# badge.net
KiCad netlist of a schematic drawn in EAGLE
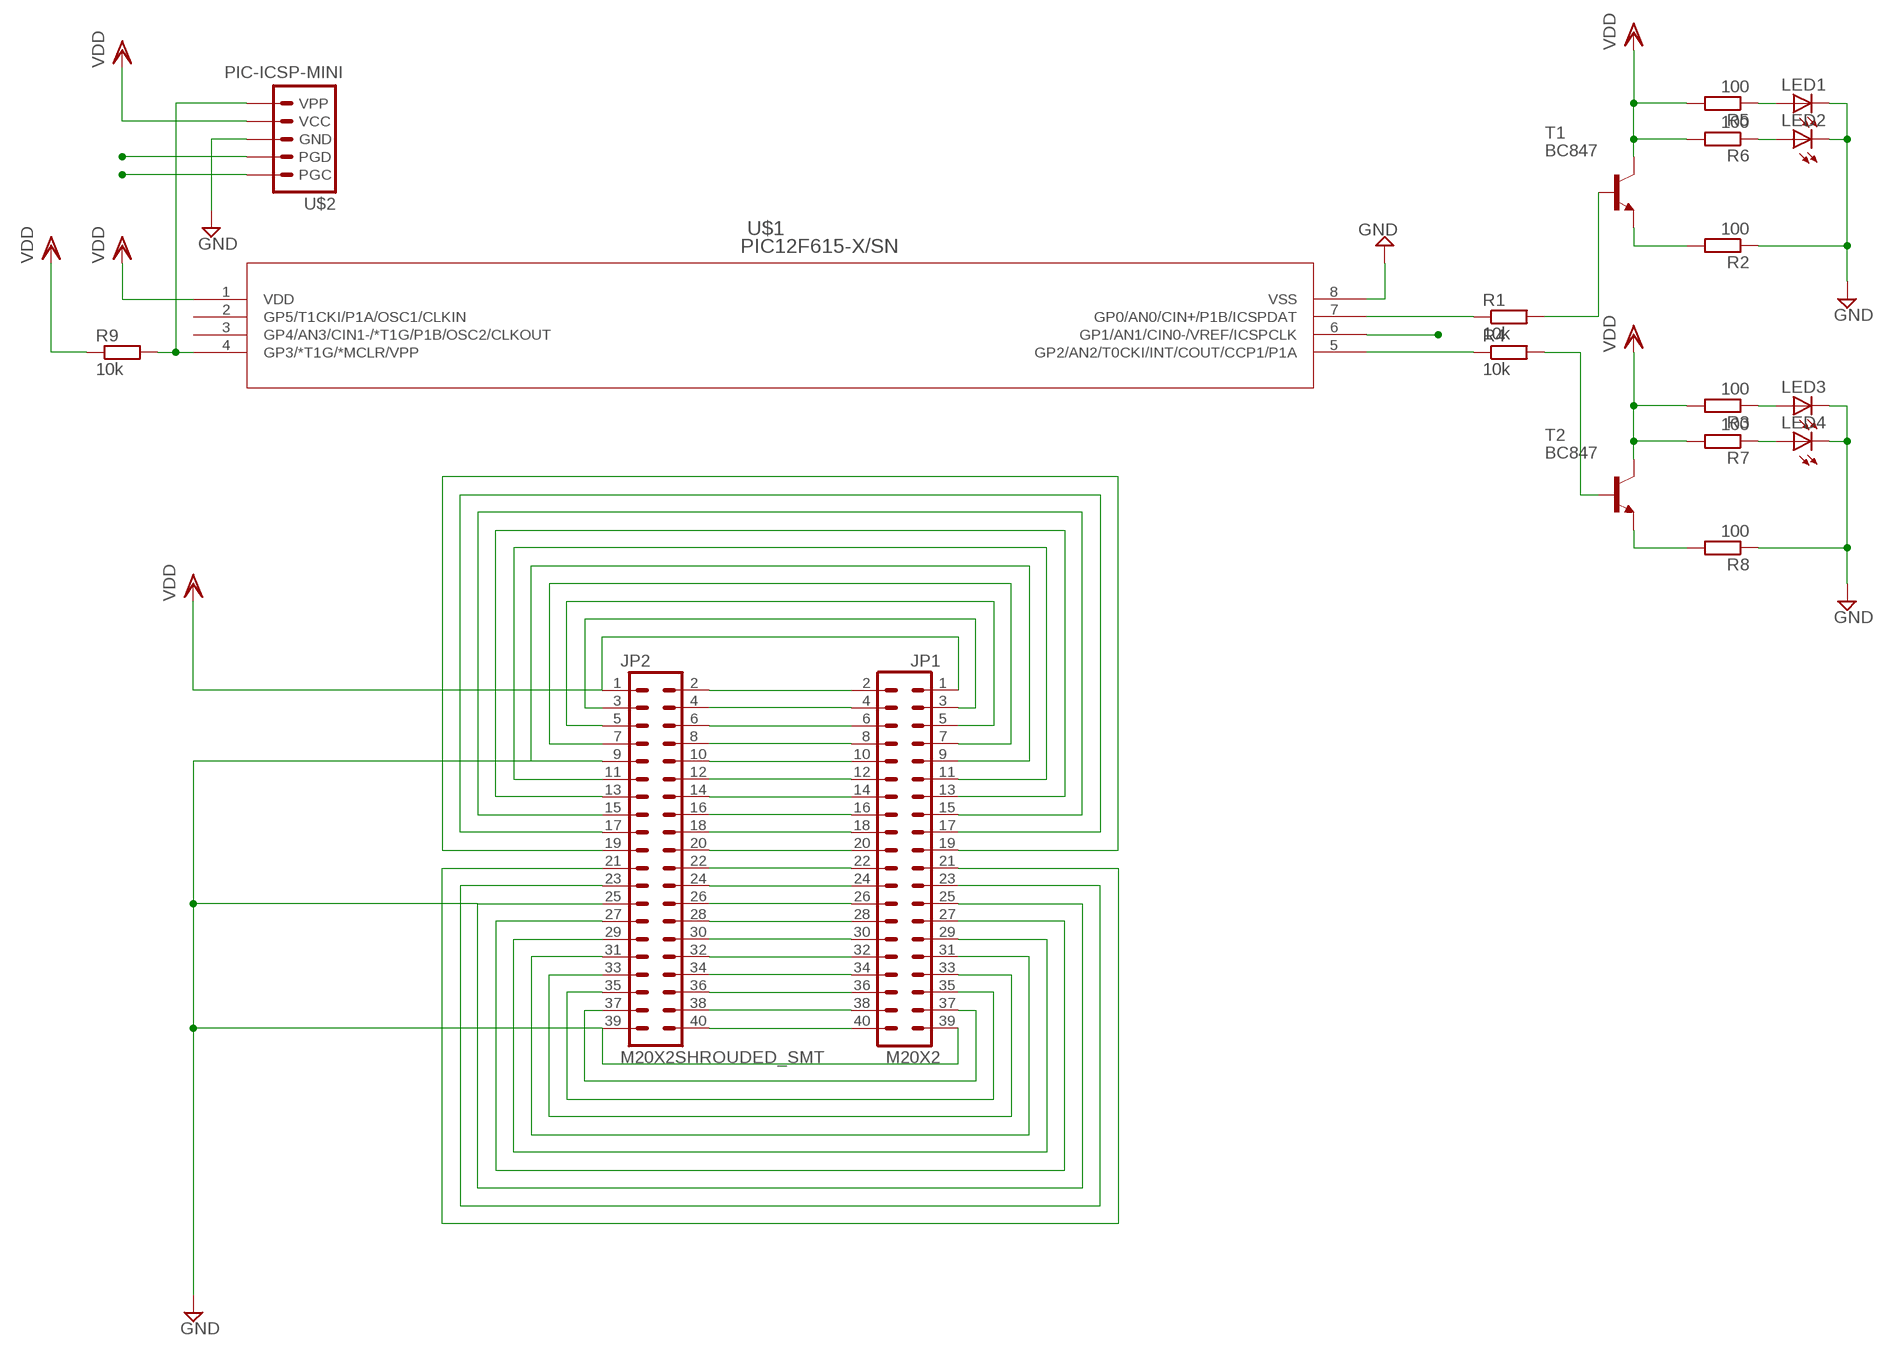
[diagram p0: schematic, sheet 1]

(export (version "E")
  (design (tool "Eeschema 10.0.6"))
  (components
    (comp (ref "JP1")
      (value "M20X2")
      (footprint "eagle-import:2X20")
      (libsource (lib "eagle-import") (part "M20X2"))
    )
    (comp (ref "JP2")
      (value "M20X2SHROUDED_SMT")
      (footprint "eagle-import:2X20_SHROUDED_SMT")
      (libsource (lib "eagle-import") (part "M20X2SHROUDED_SMT"))
    )
    (comp (ref "LED1")
      (value "LEDCHIPLED_0805")
      (footprint "eagle-import:CHIPLED_0805")
      (libsource (lib "eagle-import") (part "LEDCHIPLED_0805"))
    )
    (comp (ref "LED2")
      (value "LEDCHIPLED_0805")
      (footprint "eagle-import:CHIPLED_0805")
      (libsource (lib "eagle-import") (part "LEDCHIPLED_0805"))
    )
    (comp (ref "LED3")
      (value "LEDCHIPLED_0805")
      (footprint "eagle-import:CHIPLED_0805")
      (libsource (lib "eagle-import") (part "LEDCHIPLED_0805"))
    )
    (comp (ref "LED4")
      (value "LEDCHIPLED_0805")
      (footprint "eagle-import:CHIPLED_0805")
      (libsource (lib "eagle-import") (part "LEDCHIPLED_0805"))
    )
    (comp (ref "R1")
      (value "10k")
      (footprint "eagle-import:R0805")
      (libsource (lib "eagle-import") (part "R-EU_R0805"))
    )
    (comp (ref "R2")
      (value "100")
      (footprint "eagle-import:R0805")
      (libsource (lib "eagle-import") (part "R-EU_R0805"))
    )
    (comp (ref "R3")
      (value "100")
      (footprint "eagle-import:R0805")
      (libsource (lib "eagle-import") (part "R-EU_R0805"))
    )
    (comp (ref "R4")
      (value "10k")
      (footprint "eagle-import:R0805")
      (libsource (lib "eagle-import") (part "R-EU_R0805"))
    )
    (comp (ref "R5")
      (value "100")
      (footprint "eagle-import:R0805")
      (libsource (lib "eagle-import") (part "R-EU_R0805"))
    )
    (comp (ref "R6")
      (value "100")
      (footprint "eagle-import:R0805")
      (libsource (lib "eagle-import") (part "R-EU_R0805"))
    )
    (comp (ref "R7")
      (value "100")
      (footprint "eagle-import:R0805")
      (libsource (lib "eagle-import") (part "R-EU_R0805"))
    )
    (comp (ref "R8")
      (value "100")
      (footprint "eagle-import:R0805")
      (libsource (lib "eagle-import") (part "R-EU_R0805"))
    )
    (comp (ref "R9")
      (value "10k")
      (footprint "eagle-import:R0805")
      (libsource (lib "eagle-import") (part "R-EU_R0805"))
    )
    (comp (ref "T1")
      (value "BC847")
      (footprint "eagle-import:SOT23")
      (libsource (lib "eagle-import") (part "BC847"))
    )
    (comp (ref "T2")
      (value "BC847")
      (footprint "eagle-import:SOT23")
      (libsource (lib "eagle-import") (part "BC847"))
    )
    (comp (ref "U$1")
      (value "PIC12F615-X/SN")
      (footprint "eagle-import:SOIC8-N_MC")
      (libsource (lib "eagle-import") (part "PIC12F615-X/SN"))
    )
    (comp (ref "U$2")
      (value "PIC-ICSP-MINI")
      (footprint "eagle-import:PIC-ICSP-MINI")
      (libsource (lib "eagle-import") (part "PIC-ICSP-MINI"))
    )
  )
  (nets
    (net (code "1") (name "/ICSPCLK") (class "Default")
      (node (ref "U$1") (pin "6") (pinfunction "GP1/AN1/CIN0-/VREF/ICSPCLK_6") (pintype "passive"))
      (node (ref "U$2") (pin "5") (pinfunction "PGC_5") (pintype "passive"))
    )
    (net (code "2") (name "/ICSPDAT") (class "Default")
      (node (ref "R1") (pin "1") (pinfunction "1_1") (pintype "passive"))
      (node (ref "U$1") (pin "7") (pinfunction "GP0/AN0/CIN+/P1B/ICSPDAT_7") (pintype "passive"))
      (node (ref "U$2") (pin "4") (pinfunction "PGD_4") (pintype "passive"))
    )
    (net (code "3") (name "GND") (class "Default")
      (node (ref "JP1") (pin "14") (pinfunction "14_14") (pintype "passive"))
      (node (ref "JP1") (pin "20") (pinfunction "20_20") (pintype "passive"))
      (node (ref "JP1") (pin "25") (pinfunction "25_25") (pintype "passive"))
      (node (ref "JP1") (pin "30") (pinfunction "30_30") (pintype "passive"))
      (node (ref "JP1") (pin "34") (pinfunction "34_34") (pintype "passive"))
      (node (ref "JP1") (pin "39") (pinfunction "39_39") (pintype "passive"))
      (node (ref "JP1") (pin "6") (pinfunction "6_6") (pintype "passive"))
      (node (ref "JP1") (pin "9") (pinfunction "9_9") (pintype "passive"))
      (node (ref "JP2") (pin "14") (pinfunction "14_14") (pintype "passive"))
      (node (ref "JP2") (pin "20") (pinfunction "20_20") (pintype "passive"))
      (node (ref "JP2") (pin "25") (pinfunction "25_25") (pintype "passive"))
      (node (ref "JP2") (pin "30") (pinfunction "30_30") (pintype "passive"))
      (node (ref "JP2") (pin "34") (pinfunction "34_34") (pintype "passive"))
      (node (ref "JP2") (pin "39") (pinfunction "39_39") (pintype "passive"))
      (node (ref "JP2") (pin "6") (pinfunction "6_6") (pintype "passive"))
      (node (ref "JP2") (pin "9") (pinfunction "9_9") (pintype "passive"))
      (node (ref "LED1") (pin "C") (pinfunction "C_C") (pintype "passive"))
      (node (ref "LED2") (pin "C") (pinfunction "C_C") (pintype "passive"))
      (node (ref "LED3") (pin "C") (pinfunction "C_C") (pintype "passive"))
      (node (ref "LED4") (pin "C") (pinfunction "C_C") (pintype "passive"))
      (node (ref "R2") (pin "1") (pinfunction "1_1") (pintype "passive"))
      (node (ref "R8") (pin "1") (pinfunction "1_1") (pintype "passive"))
      (node (ref "U$1") (pin "8") (pinfunction "VSS_8") (pintype "passive"))
      (node (ref "U$2") (pin "3") (pinfunction "GND_3") (pintype "passive"))
    )
    (net (code "4") (name "Net-(JP1-Pad2)") (class "Default")
      (node (ref "JP1") (pin "2") (pinfunction "2_2") (pintype "passive"))
      (node (ref "JP2") (pin "2") (pinfunction "2_2") (pintype "passive"))
    )
    (net (code "5") (name "Net-(JP1-Pad3)") (class "Default")
      (node (ref "JP1") (pin "3") (pinfunction "3_3") (pintype "passive"))
      (node (ref "JP2") (pin "3") (pinfunction "3_3") (pintype "passive"))
    )
    (net (code "6") (name "Net-(JP1-Pad4)") (class "Default")
      (node (ref "JP1") (pin "4") (pinfunction "4_4") (pintype "passive"))
      (node (ref "JP2") (pin "4") (pinfunction "4_4") (pintype "passive"))
    )
    (net (code "7") (name "Net-(JP1-Pad5)") (class "Default")
      (node (ref "JP1") (pin "5") (pinfunction "5_5") (pintype "passive"))
      (node (ref "JP2") (pin "5") (pinfunction "5_5") (pintype "passive"))
    )
    (net (code "8") (name "Net-(JP1-Pad7)") (class "Default")
      (node (ref "JP1") (pin "7") (pinfunction "7_7") (pintype "passive"))
      (node (ref "JP2") (pin "7") (pinfunction "7_7") (pintype "passive"))
    )
    (net (code "9") (name "Net-(JP1-Pad8)") (class "Default")
      (node (ref "JP1") (pin "8") (pinfunction "8_8") (pintype "passive"))
      (node (ref "JP2") (pin "8") (pinfunction "8_8") (pintype "passive"))
    )
    (net (code "10") (name "Net-(JP1-Pad10)") (class "Default")
      (node (ref "JP1") (pin "10") (pinfunction "10_10") (pintype "passive"))
      (node (ref "JP2") (pin "10") (pinfunction "10_10") (pintype "passive"))
    )
    (net (code "11") (name "Net-(JP1-Pad11)") (class "Default")
      (node (ref "JP1") (pin "11") (pinfunction "11_11") (pintype "passive"))
      (node (ref "JP2") (pin "11") (pinfunction "11_11") (pintype "passive"))
    )
    (net (code "12") (name "Net-(JP1-Pad12)") (class "Default")
      (node (ref "JP1") (pin "12") (pinfunction "12_12") (pintype "passive"))
      (node (ref "JP2") (pin "12") (pinfunction "12_12") (pintype "passive"))
    )
    (net (code "13") (name "Net-(JP1-Pad13)") (class "Default")
      (node (ref "JP1") (pin "13") (pinfunction "13_13") (pintype "passive"))
      (node (ref "JP2") (pin "13") (pinfunction "13_13") (pintype "passive"))
    )
    (net (code "14") (name "Net-(JP1-Pad15)") (class "Default")
      (node (ref "JP1") (pin "15") (pinfunction "15_15") (pintype "passive"))
      (node (ref "JP2") (pin "15") (pinfunction "15_15") (pintype "passive"))
    )
    (net (code "15") (name "Net-(JP1-Pad16)") (class "Default")
      (node (ref "JP1") (pin "16") (pinfunction "16_16") (pintype "passive"))
      (node (ref "JP2") (pin "16") (pinfunction "16_16") (pintype "passive"))
    )
    (net (code "16") (name "Net-(JP1-Pad17)") (class "Default")
      (node (ref "JP1") (pin "17") (pinfunction "17_17") (pintype "passive"))
      (node (ref "JP2") (pin "17") (pinfunction "17_17") (pintype "passive"))
    )
    (net (code "17") (name "Net-(JP1-Pad18)") (class "Default")
      (node (ref "JP1") (pin "18") (pinfunction "18_18") (pintype "passive"))
      (node (ref "JP2") (pin "18") (pinfunction "18_18") (pintype "passive"))
    )
    (net (code "18") (name "Net-(JP1-Pad19)") (class "Default")
      (node (ref "JP1") (pin "19") (pinfunction "19_19") (pintype "passive"))
      (node (ref "JP2") (pin "19") (pinfunction "19_19") (pintype "passive"))
    )
    (net (code "19") (name "Net-(JP1-Pad21)") (class "Default")
      (node (ref "JP1") (pin "21") (pinfunction "21_21") (pintype "passive"))
      (node (ref "JP2") (pin "21") (pinfunction "21_21") (pintype "passive"))
    )
    (net (code "20") (name "Net-(JP1-Pad22)") (class "Default")
      (node (ref "JP1") (pin "22") (pinfunction "22_22") (pintype "passive"))
      (node (ref "JP2") (pin "22") (pinfunction "22_22") (pintype "passive"))
    )
    (net (code "21") (name "Net-(JP1-Pad23)") (class "Default")
      (node (ref "JP1") (pin "23") (pinfunction "23_23") (pintype "passive"))
      (node (ref "JP2") (pin "23") (pinfunction "23_23") (pintype "passive"))
    )
    (net (code "22") (name "Net-(JP1-Pad24)") (class "Default")
      (node (ref "JP1") (pin "24") (pinfunction "24_24") (pintype "passive"))
      (node (ref "JP2") (pin "24") (pinfunction "24_24") (pintype "passive"))
    )
    (net (code "23") (name "Net-(JP1-Pad26)") (class "Default")
      (node (ref "JP1") (pin "26") (pinfunction "26_26") (pintype "passive"))
      (node (ref "JP2") (pin "26") (pinfunction "26_26") (pintype "passive"))
    )
    (net (code "24") (name "Net-(JP1-Pad27)") (class "Default")
      (node (ref "JP1") (pin "27") (pinfunction "27_27") (pintype "passive"))
      (node (ref "JP2") (pin "27") (pinfunction "27_27") (pintype "passive"))
    )
    (net (code "25") (name "Net-(JP1-Pad28)") (class "Default")
      (node (ref "JP1") (pin "28") (pinfunction "28_28") (pintype "passive"))
      (node (ref "JP2") (pin "28") (pinfunction "28_28") (pintype "passive"))
    )
    (net (code "26") (name "Net-(JP1-Pad29)") (class "Default")
      (node (ref "JP1") (pin "29") (pinfunction "29_29") (pintype "passive"))
      (node (ref "JP2") (pin "29") (pinfunction "29_29") (pintype "passive"))
    )
    (net (code "27") (name "Net-(JP1-Pad31)") (class "Default")
      (node (ref "JP1") (pin "31") (pinfunction "31_31") (pintype "passive"))
      (node (ref "JP2") (pin "31") (pinfunction "31_31") (pintype "passive"))
    )
    (net (code "28") (name "Net-(JP1-Pad32)") (class "Default")
      (node (ref "JP1") (pin "32") (pinfunction "32_32") (pintype "passive"))
      (node (ref "JP2") (pin "32") (pinfunction "32_32") (pintype "passive"))
    )
    (net (code "29") (name "Net-(JP1-Pad33)") (class "Default")
      (node (ref "JP1") (pin "33") (pinfunction "33_33") (pintype "passive"))
      (node (ref "JP2") (pin "33") (pinfunction "33_33") (pintype "passive"))
    )
    (net (code "30") (name "Net-(JP1-Pad35)") (class "Default")
      (node (ref "JP1") (pin "35") (pinfunction "35_35") (pintype "passive"))
      (node (ref "JP2") (pin "35") (pinfunction "35_35") (pintype "passive"))
    )
    (net (code "31") (name "Net-(JP1-Pad36)") (class "Default")
      (node (ref "JP1") (pin "36") (pinfunction "36_36") (pintype "passive"))
      (node (ref "JP2") (pin "36") (pinfunction "36_36") (pintype "passive"))
    )
    (net (code "32") (name "Net-(JP1-Pad37)") (class "Default")
      (node (ref "JP1") (pin "37") (pinfunction "37_37") (pintype "passive"))
      (node (ref "JP2") (pin "37") (pinfunction "37_37") (pintype "passive"))
    )
    (net (code "33") (name "Net-(JP1-Pad38)") (class "Default")
      (node (ref "JP1") (pin "38") (pinfunction "38_38") (pintype "passive"))
      (node (ref "JP2") (pin "38") (pinfunction "38_38") (pintype "passive"))
    )
    (net (code "34") (name "Net-(JP1-Pad40)") (class "Default")
      (node (ref "JP1") (pin "40") (pinfunction "40_40") (pintype "passive"))
      (node (ref "JP2") (pin "40") (pinfunction "40_40") (pintype "passive"))
    )
    (net (code "35") (name "Net-(LED1-PadA)") (class "Default")
      (node (ref "LED1") (pin "A") (pinfunction "A_A") (pintype "passive"))
      (node (ref "R5") (pin "1") (pinfunction "1_1") (pintype "passive"))
    )
    (net (code "36") (name "Net-(LED2-PadA)") (class "Default")
      (node (ref "LED2") (pin "A") (pinfunction "A_A") (pintype "passive"))
      (node (ref "R6") (pin "1") (pinfunction "1_1") (pintype "passive"))
    )
    (net (code "37") (name "Net-(LED3-PadA)") (class "Default")
      (node (ref "LED3") (pin "A") (pinfunction "A_A") (pintype "passive"))
      (node (ref "R3") (pin "1") (pinfunction "1_1") (pintype "passive"))
    )
    (net (code "38") (name "Net-(LED4-PadA)") (class "Default")
      (node (ref "LED4") (pin "A") (pinfunction "A_A") (pintype "passive"))
      (node (ref "R7") (pin "1") (pinfunction "1_1") (pintype "passive"))
    )
    (net (code "39") (name "Net-(T1-B)") (class "Default")
      (node (ref "R1") (pin "2") (pinfunction "2_2") (pintype "passive"))
      (node (ref "T1") (pin "1") (pinfunction "B_1") (pintype "passive"))
    )
    (net (code "40") (name "Net-(T1-E)") (class "Default")
      (node (ref "R2") (pin "2") (pinfunction "2_2") (pintype "passive"))
      (node (ref "T1") (pin "2") (pinfunction "E_2") (pintype "passive"))
    )
    (net (code "41") (name "Net-(T2-B)") (class "Default")
      (node (ref "R4") (pin "2") (pinfunction "2_2") (pintype "passive"))
      (node (ref "T2") (pin "1") (pinfunction "B_1") (pintype "passive"))
    )
    (net (code "42") (name "Net-(T2-E)") (class "Default")
      (node (ref "R8") (pin "2") (pinfunction "2_2") (pintype "passive"))
      (node (ref "T2") (pin "2") (pinfunction "E_2") (pintype "passive"))
    )
    (net (code "43") (name "Net-(U$1-GP2{slash}AN2{slash}T0CKI{slash}INT{slash}COUT{slash}CCP1{slash}P1A)") (class "Default")
      (node (ref "R4") (pin "1") (pinfunction "1_1") (pintype "passive"))
      (node (ref "U$1") (pin "5") (pinfunction "GP2/AN2/T0CKI/INT/COUT/CCP1/P1A_5") (pintype "passive"))
    )
    (net (code "44") (name "Net-(U$1-GP3{slash}*T1G{slash}*MCLR{slash}VPP)") (class "Default")
      (node (ref "R9") (pin "2") (pinfunction "2_2") (pintype "passive"))
      (node (ref "U$1") (pin "4") (pinfunction "GP3/*T1G/*MCLR/VPP_4") (pintype "passive"))
      (node (ref "U$2") (pin "1") (pinfunction "VPP_1") (pintype "passive"))
    )
    (net (code "45") (name "VDD") (class "Default")
      (node (ref "JP1") (pin "1") (pinfunction "1_1") (pintype "passive"))
      (node (ref "JP2") (pin "1") (pinfunction "1_1") (pintype "passive"))
      (node (ref "R3") (pin "2") (pinfunction "2_2") (pintype "passive"))
      (node (ref "R5") (pin "2") (pinfunction "2_2") (pintype "passive"))
      (node (ref "R6") (pin "2") (pinfunction "2_2") (pintype "passive"))
      (node (ref "R7") (pin "2") (pinfunction "2_2") (pintype "passive"))
      (node (ref "R9") (pin "1") (pinfunction "1_1") (pintype "passive"))
      (node (ref "T1") (pin "3") (pinfunction "C_3") (pintype "passive"))
      (node (ref "T2") (pin "3") (pinfunction "C_3") (pintype "passive"))
      (node (ref "U$1") (pin "1") (pinfunction "VDD_1") (pintype "passive"))
      (node (ref "U$2") (pin "2") (pinfunction "VCC_2") (pintype "passive"))
    )
    (net (code "46") (name "unconnected-(U$1-GP4{slash}AN3{slash}CIN1-{slash}*T1G{slash}P1B{slash}OSC2{slash}CLKOUT-Pad3)") (class "Default")
      (node (ref "U$1") (pin "3") (pinfunction "GP4/AN3/CIN1-/*T1G/P1B/OSC2/CLKOUT_3") (pintype "passive"))
    )
    (net (code "47") (name "unconnected-(U$1-GP5{slash}T1CKI{slash}P1A{slash}OSC1{slash}CLKIN-Pad2)") (class "Default")
      (node (ref "U$1") (pin "2") (pinfunction "GP5/T1CKI/P1A/OSC1/CLKIN_2") (pintype "passive"))
    )
  )
)
